# old_small_line.net
KiCad netlist of a schematic drawn in EAGLE
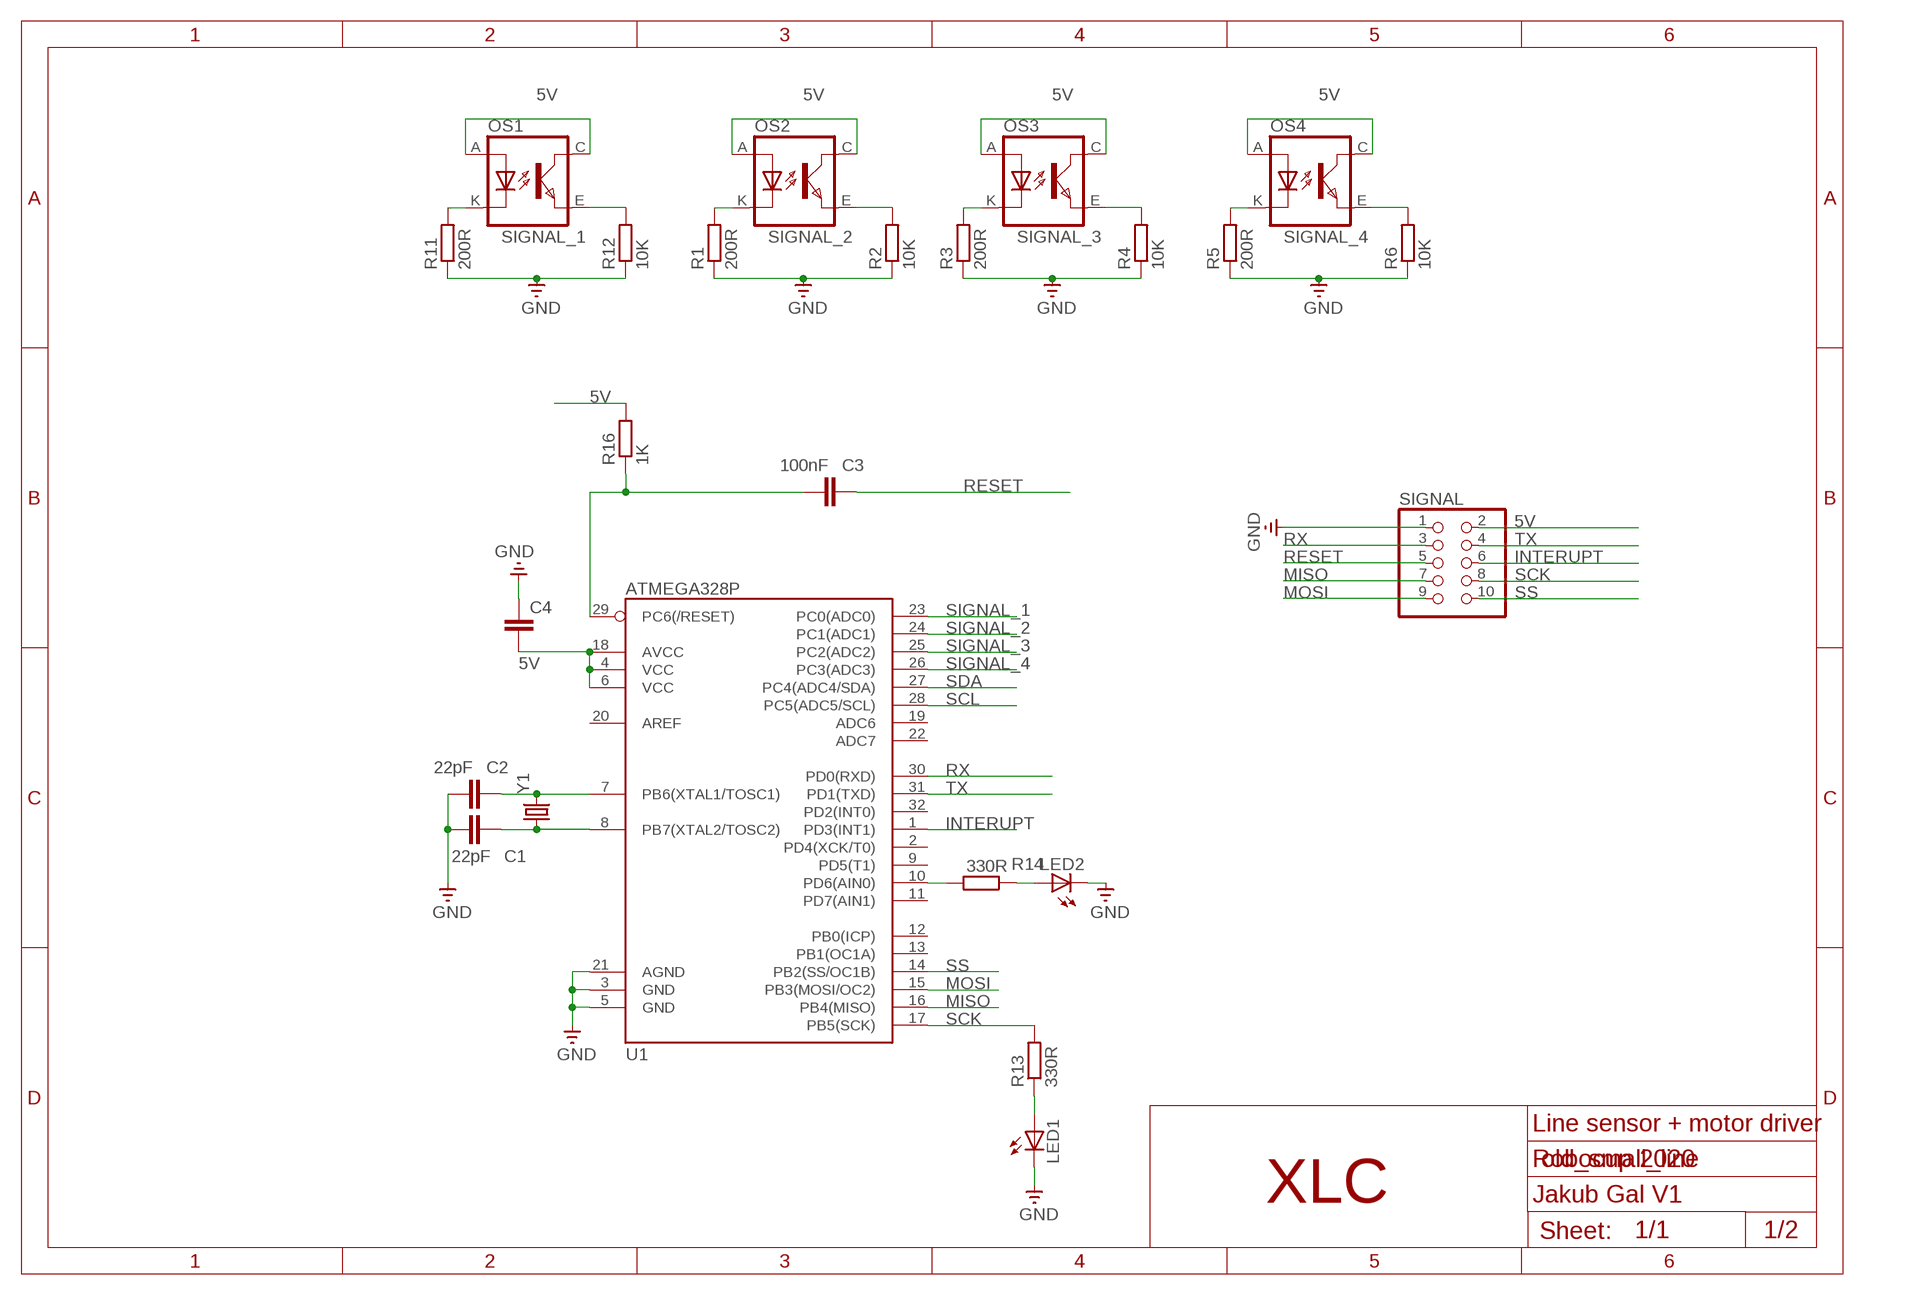
[diagram p0: schematic, sheet 1]

(export (version "E")
  (design (tool "Eeschema 10.0.6"))
  (components
    (comp (ref "C1")
      (value "22pF")
      (footprint "eagle-import:C0603")
      (libsource (lib "eagle-import") (part "rcl@1_C-EUC0603"))
    )
    (comp (ref "C2")
      (value "22pF")
      (footprint "eagle-import:C0603")
      (libsource (lib "eagle-import") (part "rcl@1_C-EUC0603"))
    )
    (comp (ref "C3")
      (value "100nF")
      (footprint "eagle-import:C0603")
      (libsource (lib "eagle-import") (part "rcl@1_C-EUC0603"))
    )
    (comp (ref "C4")
      (value "C-EUC0603")
      (footprint "eagle-import:C0603")
      (libsource (lib "eagle-import") (part "C-EUC0603"))
    )
    (comp (ref "LED1")
      (value "LEDCHIPLED_0603")
      (footprint "eagle-import:CHIPLED_0603")
      (libsource (lib "eagle-import") (part "LEDCHIPLED_0603"))
    )
    (comp (ref "LED2")
      (value "LEDCHIPLED_0603")
      (footprint "eagle-import:CHIPLED_0603")
      (libsource (lib "eagle-import") (part "LEDCHIPLED_0603"))
    )
    (comp (ref "OS1")
      (value "TCRT5000")
      (footprint "eagle-import:TCRT5000")
      (libsource (lib "eagle-import") (part "TCRT5000"))
    )
    (comp (ref "OS2")
      (value "TCRT5000")
      (footprint "eagle-import:TCRT5000")
      (libsource (lib "eagle-import") (part "TCRT5000"))
    )
    (comp (ref "OS3")
      (value "TCRT5000")
      (footprint "eagle-import:TCRT5000")
      (libsource (lib "eagle-import") (part "TCRT5000"))
    )
    (comp (ref "OS4")
      (value "TCRT5000")
      (footprint "eagle-import:TCRT5000")
      (libsource (lib "eagle-import") (part "TCRT5000"))
    )
    (comp (ref "R1")
      (value "200R")
      (footprint "eagle-import:R0603")
      (libsource (lib "eagle-import") (part "R-EU_R0603"))
    )
    (comp (ref "R2")
      (value "10K")
      (footprint "eagle-import:R0603")
      (libsource (lib "eagle-import") (part "R-EU_R0603"))
    )
    (comp (ref "R3")
      (value "200R")
      (footprint "eagle-import:R0603")
      (libsource (lib "eagle-import") (part "R-EU_R0603"))
    )
    (comp (ref "R4")
      (value "10K")
      (footprint "eagle-import:R0603")
      (libsource (lib "eagle-import") (part "R-EU_R0603"))
    )
    (comp (ref "R5")
      (value "200R")
      (footprint "eagle-import:R0603")
      (libsource (lib "eagle-import") (part "R-EU_R0603"))
    )
    (comp (ref "R6")
      (value "10K")
      (footprint "eagle-import:R0603")
      (libsource (lib "eagle-import") (part "R-EU_R0603"))
    )
    (comp (ref "R11")
      (value "200R")
      (footprint "eagle-import:R0603")
      (libsource (lib "eagle-import") (part "R-EU_R0603"))
    )
    (comp (ref "R12")
      (value "10K")
      (footprint "eagle-import:R0603")
      (libsource (lib "eagle-import") (part "R-EU_R0603"))
    )
    (comp (ref "R13")
      (value "330R")
      (footprint "eagle-import:R0603")
      (libsource (lib "eagle-import") (part "R-EU_R0603"))
    )
    (comp (ref "R14")
      (value "330R")
      (footprint "eagle-import:R0603")
      (libsource (lib "eagle-import") (part "R-EU_R0603"))
    )
    (comp (ref "R16")
      (value "1K")
      (footprint "eagle-import:R0603")
      (libsource (lib "eagle-import") (part "R-EU_R0603"))
    )
    (comp (ref "SIGNAL")
      (value "PINHD-2X5")
      (footprint "eagle-import:2X05")
      (libsource (lib "eagle-import") (part "PINHD-2X5"))
    )
    (comp (ref "U1")
      (value "ATMEGA328P")
      (footprint "eagle-import:TQFP32-08")
      (libsource (lib "eagle-import") (part "ATMEGA328_SMT"))
    )
    (comp (ref "Y1")
      (value "CRYSTALHC49US")
      (footprint "eagle-import:HC49US")
      (libsource (lib "eagle-import") (part "CRYSTALHC49US"))
    )
  )
  (nets
    (net (code "1") (name "/5V") (class "Default")
      (node (ref "C4") (pin "2") (pinfunction "2_2") (pintype "passive"))
      (node (ref "OS1") (pin "A") (pinfunction "ANODE_A") (pintype "passive"))
      (node (ref "OS1") (pin "C") (pinfunction "COLLECTOR_C") (pintype "passive"))
      (node (ref "OS2") (pin "A") (pinfunction "ANODE_A") (pintype "passive"))
      (node (ref "OS2") (pin "C") (pinfunction "COLLECTOR_C") (pintype "passive"))
      (node (ref "OS3") (pin "A") (pinfunction "ANODE_A") (pintype "passive"))
      (node (ref "OS3") (pin "C") (pinfunction "COLLECTOR_C") (pintype "passive"))
      (node (ref "OS4") (pin "A") (pinfunction "ANODE_A") (pintype "passive"))
      (node (ref "OS4") (pin "C") (pinfunction "COLLECTOR_C") (pintype "passive"))
      (node (ref "R16") (pin "2") (pinfunction "2_2") (pintype "passive"))
      (node (ref "SIGNAL") (pin "2") (pinfunction "2_2") (pintype "passive"))
      (node (ref "U1") (pin "18") (pinfunction "AVCC_18") (pintype "bidirectional"))
      (node (ref "U1") (pin "4") (pinfunction "VCC_4") (pintype "bidirectional"))
      (node (ref "U1") (pin "6") (pinfunction "VCC_6") (pintype "bidirectional"))
    )
    (net (code "2") (name "/INTERUPT") (class "Default")
      (node (ref "SIGNAL") (pin "6") (pinfunction "6_6") (pintype "passive"))
      (node (ref "U1") (pin "1") (pinfunction "PD3(INT1)_1") (pintype "bidirectional"))
    )
    (net (code "3") (name "/MISO") (class "Default")
      (node (ref "SIGNAL") (pin "7") (pinfunction "7_7") (pintype "passive"))
      (node (ref "U1") (pin "16") (pinfunction "PB4(MISO)_16") (pintype "bidirectional"))
    )
    (net (code "4") (name "/MOSI") (class "Default")
      (node (ref "SIGNAL") (pin "9") (pinfunction "9_9") (pintype "passive"))
      (node (ref "U1") (pin "15") (pinfunction "PB3(MOSI/OC2)_15") (pintype "bidirectional"))
    )
    (net (code "5") (name "/RESET") (class "Default")
      (node (ref "C3") (pin "2") (pinfunction "2_2") (pintype "passive"))
      (node (ref "SIGNAL") (pin "5") (pinfunction "5_5") (pintype "passive"))
    )
    (net (code "6") (name "/RX") (class "Default")
      (node (ref "SIGNAL") (pin "3") (pinfunction "3_3") (pintype "passive"))
      (node (ref "U1") (pin "30") (pinfunction "PD0(RXD)_30") (pintype "bidirectional"))
    )
    (net (code "7") (name "/SCK") (class "Default")
      (node (ref "R13") (pin "2") (pinfunction "2_2") (pintype "passive"))
      (node (ref "SIGNAL") (pin "8") (pinfunction "8_8") (pintype "passive"))
      (node (ref "U1") (pin "17") (pinfunction "PB5(SCK)_17") (pintype "bidirectional"))
    )
    (net (code "8") (name "/SCL") (class "Default")
      (node (ref "U1") (pin "28") (pinfunction "PC5(ADC5/SCL)_28") (pintype "bidirectional"))
    )
    (net (code "9") (name "/SDA") (class "Default")
      (node (ref "U1") (pin "27") (pinfunction "PC4(ADC4/SDA)_27") (pintype "bidirectional"))
    )
    (net (code "10") (name "/SIGNAL_1") (class "Default")
      (node (ref "OS1") (pin "E") (pinfunction "EMITTER_E") (pintype "passive"))
      (node (ref "R12") (pin "2") (pinfunction "2_2") (pintype "passive"))
      (node (ref "U1") (pin "23") (pinfunction "PC0(ADC0)_23") (pintype "bidirectional"))
    )
    (net (code "11") (name "/SIGNAL_2") (class "Default")
      (node (ref "OS2") (pin "E") (pinfunction "EMITTER_E") (pintype "passive"))
      (node (ref "R2") (pin "2") (pinfunction "2_2") (pintype "passive"))
      (node (ref "U1") (pin "24") (pinfunction "PC1(ADC1)_24") (pintype "bidirectional"))
    )
    (net (code "12") (name "/SIGNAL_3") (class "Default")
      (node (ref "OS3") (pin "E") (pinfunction "EMITTER_E") (pintype "passive"))
      (node (ref "R4") (pin "2") (pinfunction "2_2") (pintype "passive"))
      (node (ref "U1") (pin "25") (pinfunction "PC2(ADC2)_25") (pintype "bidirectional"))
    )
    (net (code "13") (name "/SIGNAL_4") (class "Default")
      (node (ref "OS4") (pin "E") (pinfunction "EMITTER_E") (pintype "passive"))
      (node (ref "R6") (pin "2") (pinfunction "2_2") (pintype "passive"))
      (node (ref "U1") (pin "26") (pinfunction "PC3(ADC3)_26") (pintype "bidirectional"))
    )
    (net (code "14") (name "/SS") (class "Default")
      (node (ref "SIGNAL") (pin "10") (pinfunction "10_10") (pintype "passive"))
      (node (ref "U1") (pin "14") (pinfunction "PB2(SS/OC1B)_14") (pintype "bidirectional"))
    )
    (net (code "15") (name "/TX") (class "Default")
      (node (ref "SIGNAL") (pin "4") (pinfunction "4_4") (pintype "passive"))
      (node (ref "U1") (pin "31") (pinfunction "PD1(TXD)_31") (pintype "bidirectional"))
    )
    (net (code "16") (name "GND") (class "Default")
      (node (ref "C1") (pin "1") (pinfunction "1_1") (pintype "passive"))
      (node (ref "C2") (pin "1") (pinfunction "1_1") (pintype "passive"))
      (node (ref "C4") (pin "1") (pinfunction "1_1") (pintype "passive"))
      (node (ref "LED1") (pin "C") (pinfunction "C_C") (pintype "passive"))
      (node (ref "LED2") (pin "C") (pinfunction "C_C") (pintype "passive"))
      (node (ref "R1") (pin "1") (pinfunction "1_1") (pintype "passive"))
      (node (ref "R11") (pin "1") (pinfunction "1_1") (pintype "passive"))
      (node (ref "R12") (pin "1") (pinfunction "1_1") (pintype "passive"))
      (node (ref "R2") (pin "1") (pinfunction "1_1") (pintype "passive"))
      (node (ref "R3") (pin "1") (pinfunction "1_1") (pintype "passive"))
      (node (ref "R4") (pin "1") (pinfunction "1_1") (pintype "passive"))
      (node (ref "R5") (pin "1") (pinfunction "1_1") (pintype "passive"))
      (node (ref "R6") (pin "1") (pinfunction "1_1") (pintype "passive"))
      (node (ref "SIGNAL") (pin "1") (pinfunction "1_1") (pintype "passive"))
      (node (ref "U1") (pin "21") (pinfunction "AGND_21") (pintype "bidirectional"))
      (node (ref "U1") (pin "3") (pinfunction "GND_3") (pintype "bidirectional"))
      (node (ref "U1") (pin "5") (pinfunction "GND_5") (pintype "bidirectional"))
    )
    (net (code "17") (name "Net-(LED1-PadA)") (class "Default")
      (node (ref "LED1") (pin "A") (pinfunction "A_A") (pintype "passive"))
      (node (ref "R13") (pin "1") (pinfunction "1_1") (pintype "passive"))
    )
    (net (code "18") (name "Net-(LED2-PadA)") (class "Default")
      (node (ref "LED2") (pin "A") (pinfunction "A_A") (pintype "passive"))
      (node (ref "R14") (pin "1") (pinfunction "1_1") (pintype "passive"))
    )
    (net (code "19") (name "Net-(OS1-CATHODE)") (class "Default")
      (node (ref "OS1") (pin "K") (pinfunction "CATHODE_K") (pintype "passive"))
      (node (ref "R11") (pin "2") (pinfunction "2_2") (pintype "passive"))
    )
    (net (code "20") (name "Net-(OS2-CATHODE)") (class "Default")
      (node (ref "OS2") (pin "K") (pinfunction "CATHODE_K") (pintype "passive"))
      (node (ref "R1") (pin "2") (pinfunction "2_2") (pintype "passive"))
    )
    (net (code "21") (name "Net-(OS3-CATHODE)") (class "Default")
      (node (ref "OS3") (pin "K") (pinfunction "CATHODE_K") (pintype "passive"))
      (node (ref "R3") (pin "2") (pinfunction "2_2") (pintype "passive"))
    )
    (net (code "22") (name "Net-(OS4-CATHODE)") (class "Default")
      (node (ref "OS4") (pin "K") (pinfunction "CATHODE_K") (pintype "passive"))
      (node (ref "R5") (pin "2") (pinfunction "2_2") (pintype "passive"))
    )
    (net (code "23") (name "Net-(U1-PB6(XTAL1{slash}TOSC1))") (class "Default")
      (node (ref "C2") (pin "2") (pinfunction "2_2") (pintype "passive"))
      (node (ref "U1") (pin "7") (pinfunction "PB6(XTAL1/TOSC1)_7") (pintype "bidirectional"))
      (node (ref "Y1") (pin "2") (pinfunction "2_2") (pintype "passive"))
    )
    (net (code "24") (name "Net-(U1-PB7(XTAL2{slash}TOSC2))") (class "Default")
      (node (ref "C1") (pin "2") (pinfunction "2_2") (pintype "passive"))
      (node (ref "U1") (pin "8") (pinfunction "PB7(XTAL2/TOSC2)_8") (pintype "bidirectional"))
      (node (ref "Y1") (pin "1") (pinfunction "1_1") (pintype "passive"))
    )
    (net (code "25") (name "Net-(U1-PC6({slash}RESET))") (class "Default")
      (node (ref "C3") (pin "1") (pinfunction "1_1") (pintype "passive"))
      (node (ref "R16") (pin "1") (pinfunction "1_1") (pintype "passive"))
      (node (ref "U1") (pin "29") (pinfunction "PC6(/RESET)_29") (pintype "bidirectional"))
    )
    (net (code "26") (name "Net-(U1-PD6(AIN0))") (class "Default")
      (node (ref "R14") (pin "2") (pinfunction "2_2") (pintype "passive"))
      (node (ref "U1") (pin "10") (pinfunction "PD6(AIN0)_10") (pintype "bidirectional"))
    )
    (net (code "27") (name "unconnected-(U1-ADC6-Pad19)") (class "Default")
      (node (ref "U1") (pin "19") (pinfunction "ADC6_19") (pintype "bidirectional"))
    )
    (net (code "28") (name "unconnected-(U1-ADC7-Pad22)") (class "Default")
      (node (ref "U1") (pin "22") (pinfunction "ADC7_22") (pintype "bidirectional"))
    )
    (net (code "29") (name "unconnected-(U1-AREF-Pad20)") (class "Default")
      (node (ref "U1") (pin "20") (pinfunction "AREF_20") (pintype "bidirectional"))
    )
    (net (code "30") (name "unconnected-(U1-PB0(ICP)-Pad12)") (class "Default")
      (node (ref "U1") (pin "12") (pinfunction "PB0(ICP)_12") (pintype "bidirectional"))
    )
    (net (code "31") (name "unconnected-(U1-PB1(OC1A)-Pad13)") (class "Default")
      (node (ref "U1") (pin "13") (pinfunction "PB1(OC1A)_13") (pintype "bidirectional"))
    )
    (net (code "32") (name "unconnected-(U1-PD2(INT0)-Pad32)") (class "Default")
      (node (ref "U1") (pin "32") (pinfunction "PD2(INT0)_32") (pintype "bidirectional"))
    )
    (net (code "33") (name "unconnected-(U1-PD4(XCK{slash}T0)-Pad2)") (class "Default")
      (node (ref "U1") (pin "2") (pinfunction "PD4(XCK/T0)_2") (pintype "bidirectional"))
    )
    (net (code "34") (name "unconnected-(U1-PD5(T1)-Pad9)") (class "Default")
      (node (ref "U1") (pin "9") (pinfunction "PD5(T1)_9") (pintype "bidirectional"))
    )
    (net (code "35") (name "unconnected-(U1-PD7(AIN1)-Pad11)") (class "Default")
      (node (ref "U1") (pin "11") (pinfunction "PD7(AIN1)_11") (pintype "bidirectional"))
    )
  )
)
